# Peripherals.net
KiCad netlist of a schematic drawn in Altium Designer
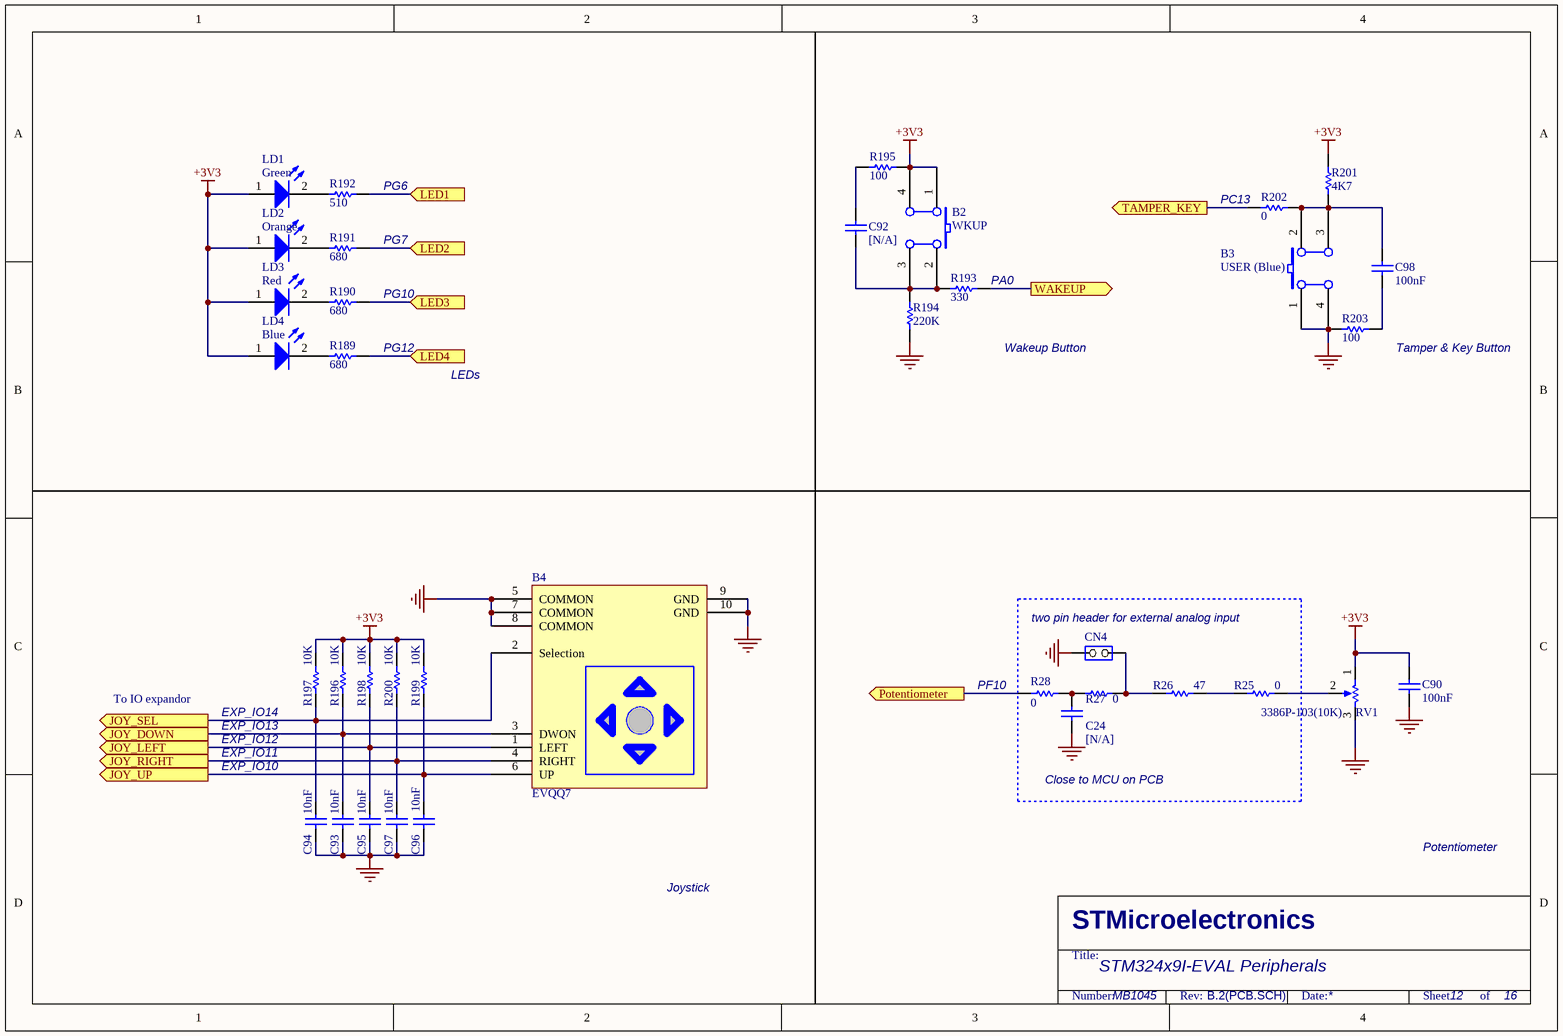
[diagram p0: Peripherals.SchDoc]

(export (version "E")
  (design (tool "Eeschema 10.0.6"))
  (components
    (comp (ref "B2")
      (value "WKUP")
      (footprint "PB10")
      (description "SE PUSHBUTTON")
      (libsource (lib "Documents") (part "SW PUSHBUTTON"))
    )
    (comp (ref "B3")
      (value "USER (Blue)")
      (footprint "PB10")
      (description "SE PUSHBUTTON")
      (libsource (lib "Documents") (part "SW PUSHBUTTON"))
    )
    (comp (ref "B4") (value "EVQQ7") (footprint "SW-JOY") (libsource (lib "mb1045") (part "EVQQ7")))
    (comp (ref "C24")
      (value "[N/A]")
      (footprint "0603C")
      (description "Capacitor")
      (fields (field (name "PUBLISHER") "Altium Limited"))
      (libsource (lib "Miscellaneous Devices") (part "cap"))
    )
    (comp (ref "C90")
      (value "100nF")
      (footprint "0603C")
      (description "Capacitor")
      (fields (field (name "PUBLISHER") "Altium Limited"))
      (libsource (lib "Miscellaneous Devices") (part "CAP"))
    )
    (comp (ref "C92")
      (value "[N/A]")
      (footprint "0603C")
      (description "Capacitor")
      (fields (field (name "PUBLISHER") "Altium Limited"))
      (libsource (lib "Miscellaneous Devices") (part "CAP"))
    )
    (comp (ref "C93")
      (value "10nF")
      (footprint "0603C")
      (description "Capacitor")
      (fields (field (name "PUBLISHER") "Altium Limited"))
      (libsource (lib "Miscellaneous Devices") (part "CAP"))
    )
    (comp (ref "C94")
      (value "10nF")
      (footprint "0603C")
      (description "Capacitor")
      (fields (field (name "PUBLISHER") "Altium Limited"))
      (libsource (lib "Miscellaneous Devices") (part "CAP"))
    )
    (comp (ref "C95")
      (value "10nF")
      (footprint "0603C")
      (description "Capacitor")
      (fields (field (name "PUBLISHER") "Altium Limited"))
      (libsource (lib "Miscellaneous Devices") (part "CAP"))
    )
    (comp (ref "C96")
      (value "10nF")
      (footprint "0603C")
      (description "Capacitor")
      (fields (field (name "PUBLISHER") "Altium Limited"))
      (libsource (lib "Miscellaneous Devices") (part "CAP"))
    )
    (comp (ref "C97")
      (value "10nF")
      (footprint "0603C")
      (description "Capacitor")
      (fields (field (name "PUBLISHER") "Altium Limited"))
      (libsource (lib "Miscellaneous Devices") (part "CAP"))
    )
    (comp (ref "C98")
      (value "100nF")
      (footprint "0603C")
      (description "Capacitor")
      (fields (field (name "PUBLISHER") "Altium Limited"))
      (libsource (lib "Miscellaneous Devices") (part "CAP"))
    )
    (comp (ref "CN4") (value "~") (footprint "SIP2") (libsource (lib "*") (part "JP2")))
    (comp (ref "LD1")
      (value "Green")
      (footprint "0603D")
      (description "Typical RED, GREEN, YELLOW, AMBER GaAs LED")
      (fields (field (name "PUBLISHER") "Altium Limited"))
      (libsource (lib "Miscellaneous Devices") (part "LED2"))
    )
    (comp (ref "LD2")
      (value "Orange")
      (footprint "0603D")
      (description "Typical RED, GREEN, YELLOW, AMBER GaAs LED")
      (fields (field (name "PUBLISHER") "Altium Limited"))
      (libsource (lib "Miscellaneous Devices") (part "LED2"))
    )
    (comp (ref "LD3")
      (value "Red")
      (footprint "0603D")
      (description "Typical RED, GREEN, YELLOW, AMBER GaAs LED")
      (fields (field (name "PUBLISHER") "Altium Limited"))
      (libsource (lib "Miscellaneous Devices") (part "LED2"))
    )
    (comp (ref "LD4")
      (value "Blue")
      (footprint "0603D")
      (description "Typical RED, GREEN, YELLOW, AMBER GaAs LED")
      (fields (field (name "PUBLISHER") "Altium Limited"))
      (libsource (lib "Miscellaneous Devices") (part "LED2"))
    )
    (comp (ref "R25")
      (value "0")
      (footprint "0603R")
      (description "Resistor")
      (fields (field (name "PUBLISHER") "Altium Limited"))
      (libsource (lib "Miscellaneous Devices") (part "Res1"))
    )
    (comp (ref "R26")
      (value "47")
      (footprint "0603R")
      (description "Resistor")
      (fields (field (name "PUBLISHER") "Altium Limited"))
      (libsource (lib "Miscellaneous Devices") (part "Res1"))
    )
    (comp (ref "R27")
      (value "0")
      (footprint "0603R")
      (description "Resistor")
      (fields (field (name "PUBLISHER") "Altium Limited"))
      (libsource (lib "Miscellaneous Devices") (part "Res1"))
    )
    (comp (ref "R28")
      (value "0")
      (footprint "0603R")
      (description "Resistor")
      (fields (field (name "PUBLISHER") "Altium Limited"))
      (libsource (lib "Miscellaneous Devices") (part "Res1"))
    )
    (comp (ref "R189")
      (value "680")
      (footprint "0603R")
      (description "Resistor")
      (fields (field (name "PUBLISHER") "Altium Limited"))
      (libsource (lib "Miscellaneous Devices") (part "Res1"))
    )
    (comp (ref "R190")
      (value "680")
      (footprint "0603R")
      (description "Resistor")
      (fields (field (name "PUBLISHER") "Altium Limited"))
      (libsource (lib "Miscellaneous Devices") (part "Res1"))
    )
    (comp (ref "R191")
      (value "680")
      (footprint "0603R")
      (description "Resistor")
      (fields (field (name "PUBLISHER") "Altium Limited"))
      (libsource (lib "Miscellaneous Devices") (part "Res1"))
    )
    (comp (ref "R192")
      (value "510")
      (footprint "0603R")
      (description "Resistor")
      (fields (field (name "PUBLISHER") "Altium Limited"))
      (libsource (lib "Miscellaneous Devices") (part "Res1"))
    )
    (comp (ref "R193")
      (value "330")
      (footprint "0603R")
      (description "Resistor")
      (fields (field (name "PUBLISHER") "Altium Limited"))
      (libsource (lib "Miscellaneous Devices") (part "Res1"))
    )
    (comp (ref "R194")
      (value "220K")
      (footprint "0603R")
      (description "Resistor")
      (fields (field (name "PUBLISHER") "Altium Limited"))
      (libsource (lib "Miscellaneous Devices") (part "res1"))
    )
    (comp (ref "R195")
      (value "100")
      (footprint "0603R")
      (description "Resistor")
      (fields (field (name "PUBLISHER") "Altium Limited"))
      (libsource (lib "Miscellaneous Devices") (part "Res1"))
    )
    (comp (ref "R196")
      (value "10K")
      (footprint "0603R")
      (description "Resistor")
      (fields (field (name "PUBLISHER") "Altium Limited"))
      (libsource (lib "Miscellaneous Devices") (part "res1"))
    )
    (comp (ref "R197")
      (value "10K")
      (footprint "0603R")
      (description "Resistor")
      (fields (field (name "PUBLISHER") "Altium Limited"))
      (libsource (lib "Miscellaneous Devices") (part "res1"))
    )
    (comp (ref "R198")
      (value "10K")
      (footprint "0603R")
      (description "Resistor")
      (fields (field (name "PUBLISHER") "Altium Limited"))
      (libsource (lib "Miscellaneous Devices") (part "res1"))
    )
    (comp (ref "R199")
      (value "10K")
      (footprint "0603R")
      (description "Resistor")
      (fields (field (name "PUBLISHER") "Altium Limited"))
      (libsource (lib "Miscellaneous Devices") (part "res1"))
    )
    (comp (ref "R200")
      (value "10K")
      (footprint "0603R")
      (description "Resistor")
      (fields (field (name "PUBLISHER") "Altium Limited"))
      (libsource (lib "Miscellaneous Devices") (part "res1"))
    )
    (comp (ref "R201")
      (value "4K7")
      (footprint "0603R")
      (description "Resistor")
      (fields (field (name "PUBLISHER") "Altium Limited"))
      (libsource (lib "Miscellaneous Devices") (part "res1"))
    )
    (comp (ref "R202")
      (value "0")
      (footprint "0603R")
      (description "Resistor")
      (fields (field (name "PUBLISHER") "Altium Limited"))
      (libsource (lib "Miscellaneous Devices") (part "Res1"))
    )
    (comp (ref "R203")
      (value "100")
      (footprint "0603R")
      (description "Resistor")
      (fields (field (name "PUBLISHER") "Altium Limited"))
      (libsource (lib "Miscellaneous Devices") (part "Res1"))
    )
    (comp (ref "RV1")
      (value "3386P-103(10K)")
      (footprint "3386P")
      (libsource (lib "STR910_SCHLIB") (part "RV"))
    )
  )
  (nets
    (net (code "1") (name "+3V3") (class "Default")
      (node (ref "B2") (pin "1") (pinfunction "A0_1") (pintype "passive"))
      (node (ref "B2") (pin "4") (pinfunction "A1_4") (pintype "passive"))
      (node (ref "C90") (pin "1") (pinfunction "1_1") (pintype "passive"))
      (node (ref "LD1") (pin "1") (pinfunction "A_1") (pintype "passive"))
      (node (ref "LD2") (pin "1") (pinfunction "A_1") (pintype "passive"))
      (node (ref "LD3") (pin "1") (pinfunction "A_1") (pintype "passive"))
      (node (ref "LD4") (pin "1") (pinfunction "A_1") (pintype "passive"))
      (node (ref "R195") (pin "1") (pinfunction "1_1") (pintype "passive"))
      (node (ref "R196") (pin "1") (pinfunction "1_1") (pintype "passive"))
      (node (ref "R197") (pin "1") (pinfunction "1_1") (pintype "passive"))
      (node (ref "R198") (pin "1") (pinfunction "1_1") (pintype "passive"))
      (node (ref "R199") (pin "1") (pinfunction "1_1") (pintype "passive"))
      (node (ref "R200") (pin "1") (pinfunction "1_1") (pintype "passive"))
      (node (ref "R201") (pin "2") (pinfunction "2_2") (pintype "passive"))
      (node (ref "RV1") (pin "1") (pinfunction "BOT_1") (pintype "passive"))
    )
    (net (code "2") (name "/JOY_DOWN") (class "Default")
      (node (ref "B4") (pin "3") (pinfunction "DWON_3") (pintype "passive"))
      (node (ref "C93") (pin "2") (pinfunction "2_2") (pintype "passive"))
      (node (ref "R196") (pin "2") (pinfunction "2_2") (pintype "passive"))
    )
    (net (code "3") (name "/JOY_LEFT") (class "Default")
      (node (ref "B4") (pin "1") (pinfunction "LEFT_1") (pintype "passive"))
      (node (ref "C95") (pin "2") (pinfunction "2_2") (pintype "passive"))
      (node (ref "R198") (pin "2") (pinfunction "2_2") (pintype "passive"))
    )
    (net (code "4") (name "/JOY_RIGHT") (class "Default")
      (node (ref "B4") (pin "4") (pinfunction "RIGHT_4") (pintype "passive"))
      (node (ref "C97") (pin "2") (pinfunction "2_2") (pintype "passive"))
      (node (ref "R200") (pin "2") (pinfunction "2_2") (pintype "passive"))
    )
    (net (code "5") (name "/JOY_SEL") (class "Default")
      (node (ref "B4") (pin "2") (pinfunction "Selection_2") (pintype "passive"))
      (node (ref "C94") (pin "2") (pinfunction "2_2") (pintype "passive"))
      (node (ref "R197") (pin "2") (pinfunction "2_2") (pintype "passive"))
    )
    (net (code "6") (name "/JOY_UP") (class "Default")
      (node (ref "B4") (pin "6") (pinfunction "UP_6") (pintype "passive"))
      (node (ref "C96") (pin "2") (pinfunction "2_2") (pintype "passive"))
      (node (ref "R199") (pin "2") (pinfunction "2_2") (pintype "passive"))
    )
    (net (code "7") (name "/LED1") (class "Default")
      (node (ref "R192") (pin "1") (pinfunction "1_1") (pintype "passive"))
    )
    (net (code "8") (name "/LED2") (class "Default")
      (node (ref "R191") (pin "1") (pinfunction "1_1") (pintype "passive"))
    )
    (net (code "9") (name "/LED3") (class "Default")
      (node (ref "R190") (pin "1") (pinfunction "1_1") (pintype "passive"))
    )
    (net (code "10") (name "/LED4") (class "Default")
      (node (ref "R189") (pin "1") (pinfunction "1_1") (pintype "passive"))
    )
    (net (code "11") (name "/Potentiometer") (class "Default")
      (node (ref "R28") (pin "2") (pinfunction "2_2") (pintype "passive"))
    )
    (net (code "12") (name "/TAMPER_KEY") (class "Default")
      (node (ref "R202") (pin "2") (pinfunction "2_2") (pintype "passive"))
    )
    (net (code "13") (name "/WAKEUP") (class "Default")
      (node (ref "R193") (pin "2") (pinfunction "2_2") (pintype "passive"))
    )
    (net (code "14") (name "GND") (class "Default")
      (node (ref "B3") (pin "1") (pinfunction "A0_1") (pintype "passive"))
      (node (ref "B3") (pin "4") (pinfunction "A1_4") (pintype "passive"))
      (node (ref "B4") (pin "10") (pinfunction "GND_10") (pintype "passive"))
      (node (ref "B4") (pin "5") (pinfunction "COMMON_5") (pintype "passive"))
      (node (ref "B4") (pin "7") (pinfunction "COMMON_7") (pintype "passive"))
      (node (ref "B4") (pin "8") (pinfunction "COMMON_8") (pintype "passive"))
      (node (ref "B4") (pin "9") (pinfunction "GND_9") (pintype "passive"))
      (node (ref "C24") (pin "1") (pinfunction "1_1") (pintype "passive"))
      (node (ref "C90") (pin "2") (pinfunction "2_2") (pintype "passive"))
      (node (ref "C93") (pin "1") (pinfunction "1_1") (pintype "passive"))
      (node (ref "C94") (pin "1") (pinfunction "1_1") (pintype "passive"))
      (node (ref "C95") (pin "1") (pinfunction "1_1") (pintype "passive"))
      (node (ref "C96") (pin "1") (pinfunction "1_1") (pintype "passive"))
      (node (ref "C97") (pin "1") (pinfunction "1_1") (pintype "passive"))
      (node (ref "CN4") (pin "2") (pinfunction "NO_2") (pintype "passive"))
      (node (ref "R194") (pin "2") (pinfunction "2_2") (pintype "passive"))
      (node (ref "R203") (pin "1") (pinfunction "1_1") (pintype "passive"))
      (node (ref "RV1") (pin "3") (pinfunction "TOP_3") (pintype "passive"))
    )
    (net (code "15") (name "Net-(B2-B0)") (class "Default")
      (node (ref "B2") (pin "2") (pinfunction "B0_2") (pintype "passive"))
      (node (ref "B2") (pin "3") (pinfunction "B1_3") (pintype "passive"))
      (node (ref "C92") (pin "2") (pinfunction "2_2") (pintype "passive"))
      (node (ref "R193") (pin "1") (pinfunction "1_1") (pintype "passive"))
      (node (ref "R194") (pin "1") (pinfunction "1_1") (pintype "passive"))
    )
    (net (code "16") (name "Net-(B3-B0)") (class "Default")
      (node (ref "B3") (pin "2") (pinfunction "B0_2") (pintype "passive"))
      (node (ref "B3") (pin "3") (pinfunction "B1_3") (pintype "passive"))
      (node (ref "C98") (pin "2") (pinfunction "2_2") (pintype "passive"))
      (node (ref "R201") (pin "1") (pinfunction "1_1") (pintype "passive"))
      (node (ref "R202") (pin "1") (pinfunction "1_1") (pintype "passive"))
    )
    (net (code "17") (name "Net-(C24-Pad2)") (class "Default")
      (node (ref "C24") (pin "2") (pinfunction "2_2") (pintype "passive"))
      (node (ref "R27") (pin "1") (pinfunction "1_1") (pintype "passive"))
      (node (ref "R28") (pin "1") (pinfunction "1_1") (pintype "passive"))
    )
    (net (code "18") (name "Net-(C92-Pad1)") (class "Default")
      (node (ref "C92") (pin "1") (pinfunction "1_1") (pintype "passive"))
      (node (ref "R195") (pin "2") (pinfunction "2_2") (pintype "passive"))
    )
    (net (code "19") (name "Net-(C98-Pad1)") (class "Default")
      (node (ref "C98") (pin "1") (pinfunction "1_1") (pintype "passive"))
      (node (ref "R203") (pin "2") (pinfunction "2_2") (pintype "passive"))
    )
    (net (code "20") (name "Net-(CN4-COMMON)") (class "Default")
      (node (ref "CN4") (pin "1") (pinfunction "COMMON_1") (pintype "passive"))
      (node (ref "R26") (pin "1") (pinfunction "1_1") (pintype "passive"))
      (node (ref "R27") (pin "2") (pinfunction "2_2") (pintype "passive"))
    )
    (net (code "21") (name "Net-(LD1-K)") (class "Default")
      (node (ref "LD1") (pin "2") (pinfunction "K_2") (pintype "passive"))
      (node (ref "R192") (pin "2") (pinfunction "2_2") (pintype "passive"))
    )
    (net (code "22") (name "Net-(LD2-K)") (class "Default")
      (node (ref "LD2") (pin "2") (pinfunction "K_2") (pintype "passive"))
      (node (ref "R191") (pin "2") (pinfunction "2_2") (pintype "passive"))
    )
    (net (code "23") (name "Net-(LD3-K)") (class "Default")
      (node (ref "LD3") (pin "2") (pinfunction "K_2") (pintype "passive"))
      (node (ref "R190") (pin "2") (pinfunction "2_2") (pintype "passive"))
    )
    (net (code "24") (name "Net-(LD4-K)") (class "Default")
      (node (ref "LD4") (pin "2") (pinfunction "K_2") (pintype "passive"))
      (node (ref "R189") (pin "2") (pinfunction "2_2") (pintype "passive"))
    )
    (net (code "25") (name "Net-(R25-Pad1)") (class "Default")
      (node (ref "R25") (pin "1") (pinfunction "1_1") (pintype "passive"))
      (node (ref "R26") (pin "2") (pinfunction "2_2") (pintype "passive"))
    )
    (net (code "26") (name "Net-(RV1-TAP)") (class "Default")
      (node (ref "R25") (pin "2") (pinfunction "2_2") (pintype "passive"))
      (node (ref "RV1") (pin "2") (pinfunction "TAP_2") (pintype "passive"))
    )
  )
)
